# Whitespace_Daughtercard_pwr.net
KiCad netlist of a schematic drawn in Altium Designer
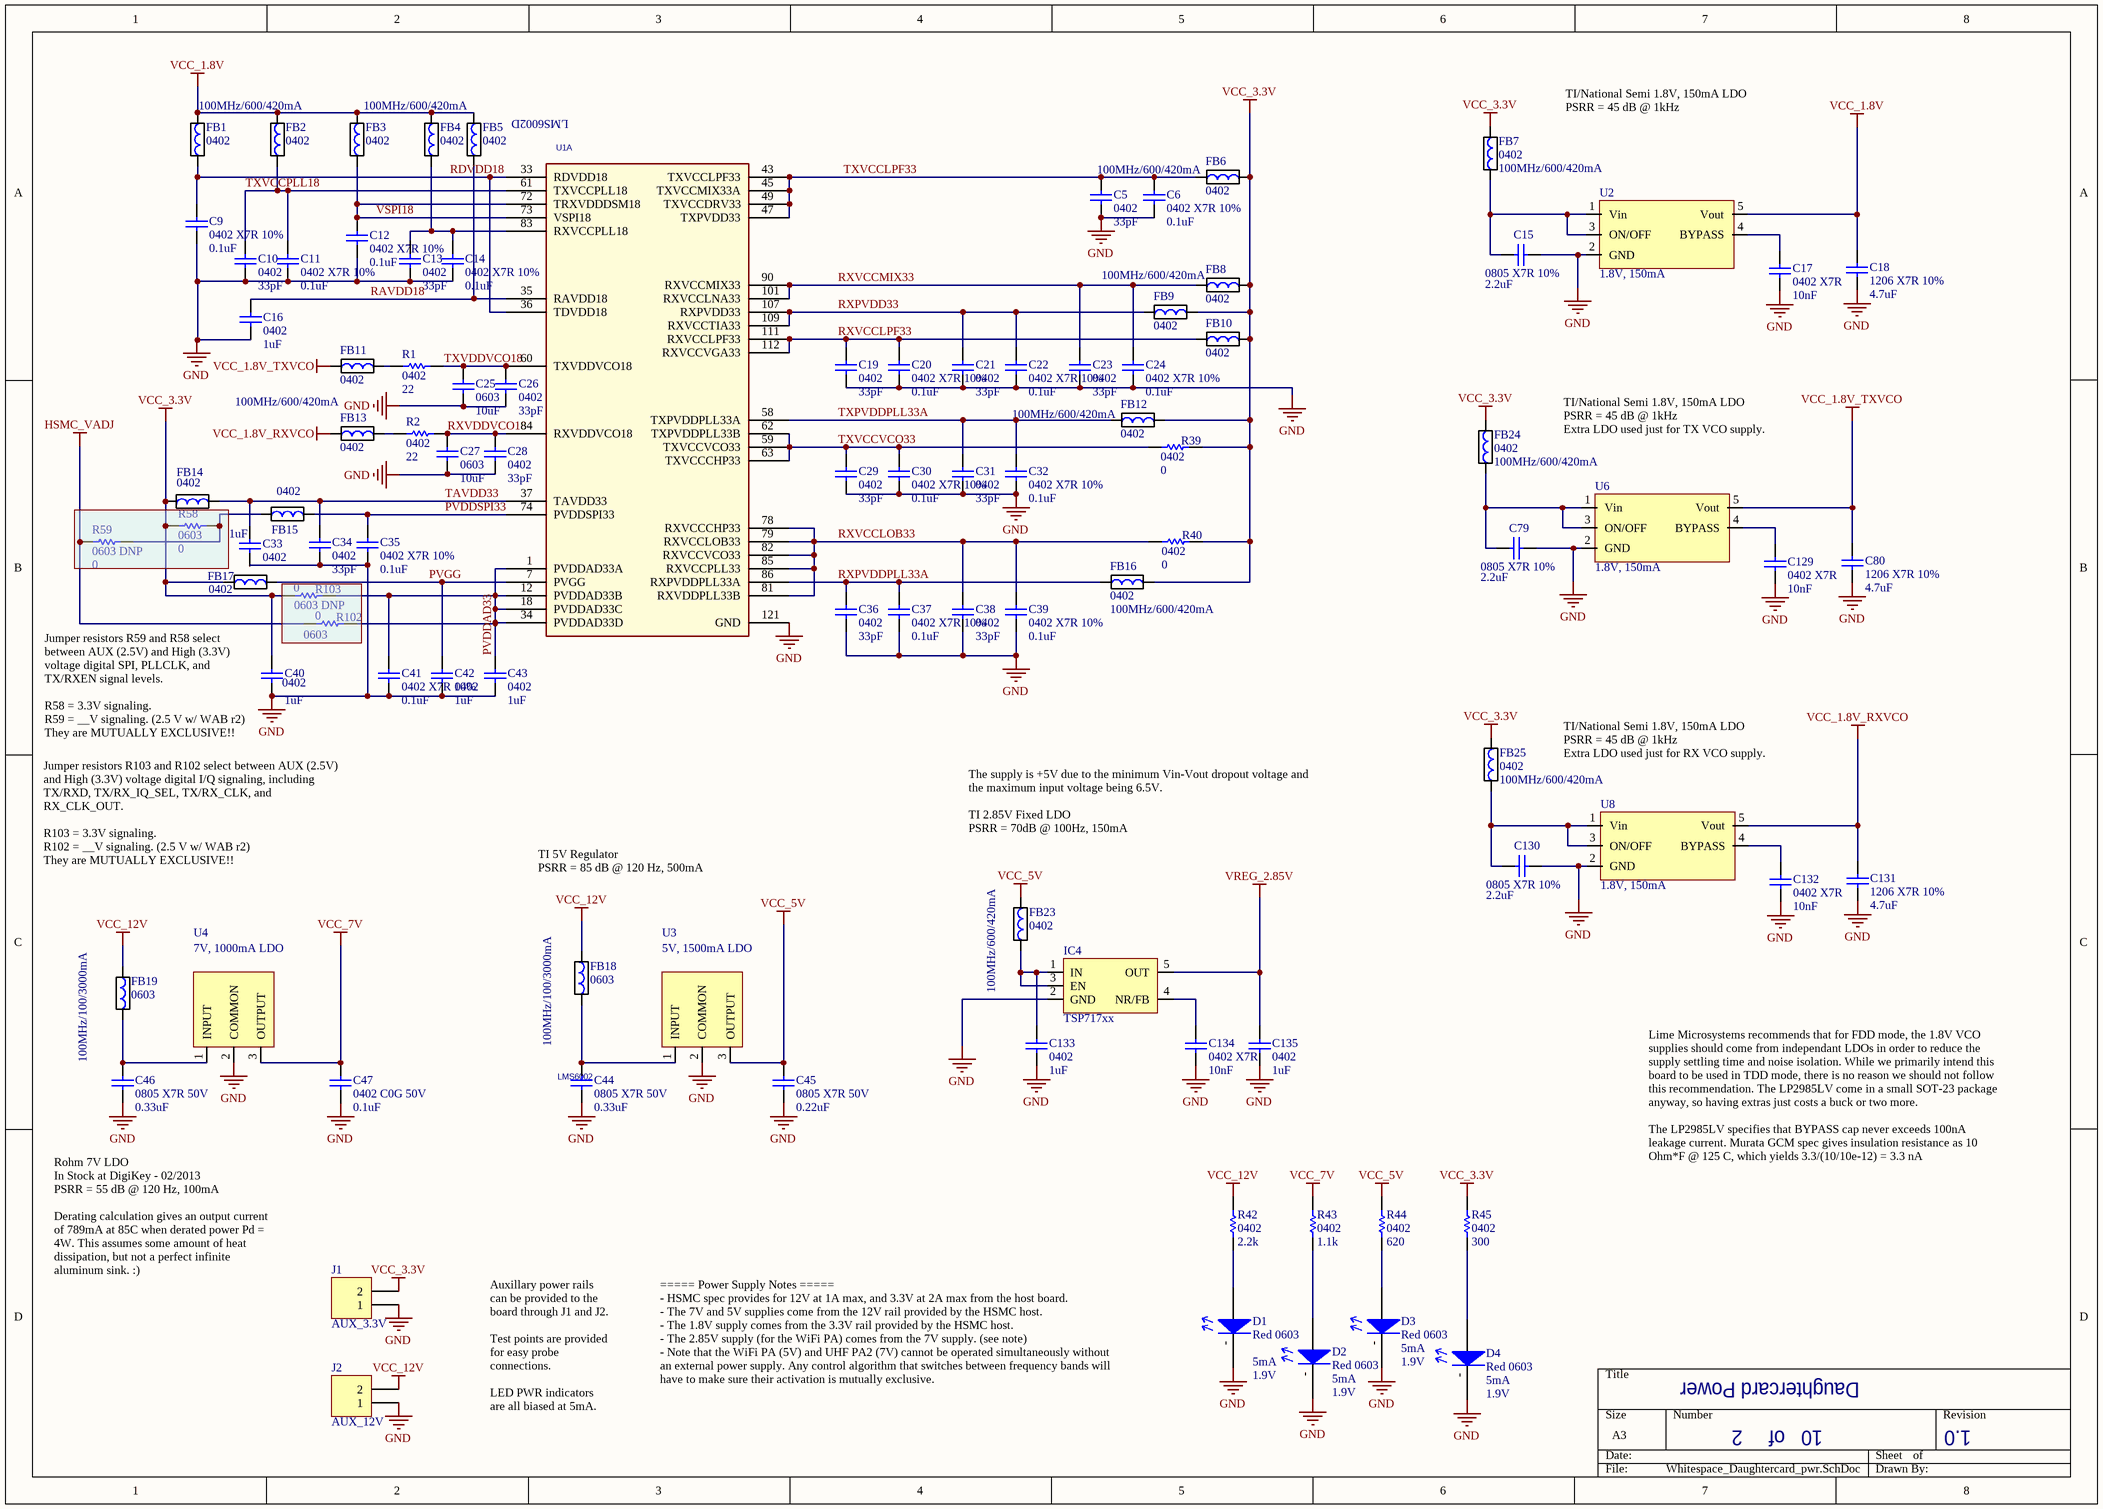
[diagram p0: Whitespace_Daughtercard_pwr.SchDoc]

(export (version "E")
  (design (tool "Eeschema 10.0.6"))
  (components
    (comp (ref "C5")
      (value "0402")
      (footprint "0402_SMT_v3")
      (description "Capacitor (Semiconductor SIM Model)")
      (fields (field (name "ALTIUM_VALUE") "33pF") (field (name "PUBLISHER") "Altium Limited"))
      (libsource (lib "Miscellaneous Devices") (part "Cap Semi"))
    )
    (comp (ref "C6")
      (value "0402 X7R 10%")
      (footprint "0402_SMT_v3")
      (description "Capacitor (Semiconductor SIM Model)")
      (fields (field (name "ALTIUM_VALUE") "0.1uF") (field (name "PUBLISHER") "Altium Limited"))
      (libsource (lib "Miscellaneous Devices") (part "Cap Semi"))
    )
    (comp (ref "C9")
      (value "0402 X7R 10%")
      (footprint "0402_SMT_v3")
      (description "Capacitor (Semiconductor SIM Model)")
      (fields (field (name "ALTIUM_VALUE") "0.1uF") (field (name "PUBLISHER") "Altium Limited"))
      (libsource (lib "Miscellaneous Devices") (part "Cap Semi"))
    )
    (comp (ref "C10")
      (value "0402")
      (footprint "0402_SMT_v3")
      (description "Capacitor (Semiconductor SIM Model)")
      (fields (field (name "ALTIUM_VALUE") "33pF") (field (name "PUBLISHER") "Altium Limited"))
      (libsource (lib "Miscellaneous Devices") (part "Cap Semi"))
    )
    (comp (ref "C11")
      (value "0402 X7R 10%")
      (footprint "0402_SMT_v3")
      (description "Capacitor (Semiconductor SIM Model)")
      (fields (field (name "ALTIUM_VALUE") "0.1uF") (field (name "PUBLISHER") "Altium Limited"))
      (libsource (lib "Miscellaneous Devices") (part "Cap Semi"))
    )
    (comp (ref "C12")
      (value "0402 X7R 10%")
      (footprint "0402_SMT_v3")
      (description "Capacitor (Semiconductor SIM Model)")
      (fields (field (name "ALTIUM_VALUE") "0.1uF") (field (name "PUBLISHER") "Altium Limited"))
      (libsource (lib "Miscellaneous Devices") (part "Cap Semi"))
    )
    (comp (ref "C13")
      (value "0402")
      (footprint "0402_SMT_v3")
      (description "Capacitor (Semiconductor SIM Model)")
      (fields (field (name "ALTIUM_VALUE") "33pF") (field (name "PUBLISHER") "Altium Limited"))
      (libsource (lib "Miscellaneous Devices") (part "Cap Semi"))
    )
    (comp (ref "C14")
      (value "0402 X7R 10%")
      (footprint "0402_SMT_v3")
      (description "Capacitor (Semiconductor SIM Model)")
      (fields (field (name "ALTIUM_VALUE") "0.1uF") (field (name "PUBLISHER") "Altium Limited"))
      (libsource (lib "Miscellaneous Devices") (part "Cap Semi"))
    )
    (comp (ref "C15")
      (value "0805 X7R 10%")
      (footprint "0805_SMT_v3")
      (description "Capacitor (Semiconductor SIM Model)")
      (fields (field (name "ALTIUM_VALUE") "2.2uF") (field (name "PUBLISHER") "Altium Limited"))
      (libsource (lib "Miscellaneous Devices") (part "Cap Semi"))
    )
    (comp (ref "C16")
      (value "0402")
      (footprint "0402_SMT_v3")
      (description "Capacitor (Semiconductor SIM Model)")
      (fields (field (name "ALTIUM_VALUE") "1uF") (field (name "PUBLISHER") "Altium Limited"))
      (libsource (lib "Miscellaneous Devices") (part "Cap Semi"))
    )
    (comp (ref "C17")
      (value "0402 X7R")
      (footprint "0402_SMT_v3")
      (description "Capacitor (Semiconductor SIM Model)")
      (fields (field (name "ALTIUM_VALUE") "10nF") (field (name "PUBLISHER") "Altium Limited"))
      (libsource (lib "Miscellaneous Devices") (part "Cap Semi"))
    )
    (comp (ref "C18")
      (value "1206 X7R 10%")
      (footprint "1206_SMT_v3")
      (description "Capacitor (Semiconductor SIM Model)")
      (fields (field (name "ALTIUM_VALUE") "4.7uF") (field (name "PUBLISHER") "Altium Limited"))
      (libsource (lib "Miscellaneous Devices") (part "Cap Semi"))
    )
    (comp (ref "C19")
      (value "0402")
      (footprint "0402_SMT_v3")
      (description "Capacitor (Semiconductor SIM Model)")
      (fields (field (name "ALTIUM_VALUE") "33pF") (field (name "PUBLISHER") "Altium Limited"))
      (libsource (lib "Miscellaneous Devices") (part "Cap Semi"))
    )
    (comp (ref "C20")
      (value "0402 X7R 10%")
      (footprint "0402_SMT_v3")
      (description "Capacitor (Semiconductor SIM Model)")
      (fields (field (name "ALTIUM_VALUE") "0.1uF") (field (name "PUBLISHER") "Altium Limited"))
      (libsource (lib "Miscellaneous Devices") (part "Cap Semi"))
    )
    (comp (ref "C21")
      (value "0402")
      (footprint "0402_SMT_v3")
      (description "Capacitor (Semiconductor SIM Model)")
      (fields (field (name "ALTIUM_VALUE") "33pF") (field (name "PUBLISHER") "Altium Limited"))
      (libsource (lib "Miscellaneous Devices") (part "Cap Semi"))
    )
    (comp (ref "C22")
      (value "0402 X7R 10%")
      (footprint "0402_SMT_v3")
      (description "Capacitor (Semiconductor SIM Model)")
      (fields (field (name "ALTIUM_VALUE") "0.1uF") (field (name "PUBLISHER") "Altium Limited"))
      (libsource (lib "Miscellaneous Devices") (part "Cap Semi"))
    )
    (comp (ref "C23")
      (value "0402")
      (footprint "0402_SMT_v3")
      (description "Capacitor (Semiconductor SIM Model)")
      (fields (field (name "ALTIUM_VALUE") "33pF") (field (name "PUBLISHER") "Altium Limited"))
      (libsource (lib "Miscellaneous Devices") (part "Cap Semi"))
    )
    (comp (ref "C24")
      (value "0402 X7R 10%")
      (footprint "0402_SMT_v3")
      (description "Capacitor (Semiconductor SIM Model)")
      (fields (field (name "ALTIUM_VALUE") "0.1uF") (field (name "PUBLISHER") "Altium Limited"))
      (libsource (lib "Miscellaneous Devices") (part "Cap Semi"))
    )
    (comp (ref "C25")
      (value "0603")
      (footprint "0603_SMT_v3")
      (description "Capacitor (Semiconductor SIM Model)")
      (fields (field (name "ALTIUM_VALUE") "10uF") (field (name "PUBLISHER") "Altium Limited"))
      (libsource (lib "Miscellaneous Devices") (part "Cap Semi"))
    )
    (comp (ref "C26")
      (value "0402")
      (footprint "0402_SMT_v3")
      (description "Capacitor (Semiconductor SIM Model)")
      (fields (field (name "ALTIUM_VALUE") "33pF") (field (name "PUBLISHER") "Altium Limited"))
      (libsource (lib "Miscellaneous Devices") (part "Cap Semi"))
    )
    (comp (ref "C27")
      (value "0603")
      (footprint "0603_SMT_v3")
      (description "Capacitor (Semiconductor SIM Model)")
      (fields (field (name "ALTIUM_VALUE") "10uF") (field (name "PUBLISHER") "Altium Limited"))
      (libsource (lib "Miscellaneous Devices") (part "Cap Semi"))
    )
    (comp (ref "C28")
      (value "0402")
      (footprint "0402_SMT_v3")
      (description "Capacitor (Semiconductor SIM Model)")
      (fields (field (name "ALTIUM_VALUE") "33pF") (field (name "PUBLISHER") "Altium Limited"))
      (libsource (lib "Miscellaneous Devices") (part "Cap Semi"))
    )
    (comp (ref "C29")
      (value "0402")
      (footprint "0402_SMT_v3")
      (description "Capacitor (Semiconductor SIM Model)")
      (fields (field (name "ALTIUM_VALUE") "33pF") (field (name "PUBLISHER") "Altium Limited"))
      (libsource (lib "Miscellaneous Devices") (part "Cap Semi"))
    )
    (comp (ref "C30")
      (value "0402 X7R 10%")
      (footprint "0402_SMT_v3")
      (description "Capacitor (Semiconductor SIM Model)")
      (fields (field (name "ALTIUM_VALUE") "0.1uF") (field (name "PUBLISHER") "Altium Limited"))
      (libsource (lib "Miscellaneous Devices") (part "Cap Semi"))
    )
    (comp (ref "C31")
      (value "0402")
      (footprint "0402_SMT_v3")
      (description "Capacitor (Semiconductor SIM Model)")
      (fields (field (name "ALTIUM_VALUE") "33pF") (field (name "PUBLISHER") "Altium Limited"))
      (libsource (lib "Miscellaneous Devices") (part "Cap Semi"))
    )
    (comp (ref "C32")
      (value "0402 X7R 10%")
      (footprint "0402_SMT_v3")
      (description "Capacitor (Semiconductor SIM Model)")
      (fields (field (name "ALTIUM_VALUE") "0.1uF") (field (name "PUBLISHER") "Altium Limited"))
      (libsource (lib "Miscellaneous Devices") (part "Cap Semi"))
    )
    (comp (ref "C33")
      (value "0402")
      (footprint "0402_SMT_v3")
      (description "Capacitor (Semiconductor SIM Model)")
      (fields (field (name "ALTIUM_VALUE") "1uF") (field (name "PUBLISHER") "Altium Limited"))
      (libsource (lib "Miscellaneous Devices") (part "Cap Semi"))
    )
    (comp (ref "C34")
      (value "0402")
      (footprint "0402_SMT_v3")
      (description "Capacitor (Semiconductor SIM Model)")
      (fields (field (name "ALTIUM_VALUE") "33pF") (field (name "PUBLISHER") "Altium Limited"))
      (libsource (lib "Miscellaneous Devices") (part "Cap Semi"))
    )
    (comp (ref "C35")
      (value "0402 X7R 10%")
      (footprint "0402_SMT_v3")
      (description "Capacitor (Semiconductor SIM Model)")
      (fields (field (name "ALTIUM_VALUE") "0.1uF") (field (name "PUBLISHER") "Altium Limited"))
      (libsource (lib "Miscellaneous Devices") (part "Cap Semi"))
    )
    (comp (ref "C36")
      (value "0402")
      (footprint "0402_SMT_v3")
      (description "Capacitor (Semiconductor SIM Model)")
      (fields (field (name "ALTIUM_VALUE") "33pF") (field (name "PUBLISHER") "Altium Limited"))
      (libsource (lib "Miscellaneous Devices") (part "Cap Semi"))
    )
    (comp (ref "C37")
      (value "0402 X7R 10%")
      (footprint "0402_SMT_v3")
      (description "Capacitor (Semiconductor SIM Model)")
      (fields (field (name "ALTIUM_VALUE") "0.1uF") (field (name "PUBLISHER") "Altium Limited"))
      (libsource (lib "Miscellaneous Devices") (part "Cap Semi"))
    )
    (comp (ref "C38")
      (value "0402")
      (footprint "0402_SMT_v3")
      (description "Capacitor (Semiconductor SIM Model)")
      (fields (field (name "ALTIUM_VALUE") "33pF") (field (name "PUBLISHER") "Altium Limited"))
      (libsource (lib "Miscellaneous Devices") (part "Cap Semi"))
    )
    (comp (ref "C39")
      (value "0402 X7R 10%")
      (footprint "0402_SMT_v3")
      (description "Capacitor (Semiconductor SIM Model)")
      (fields (field (name "ALTIUM_VALUE") "0.1uF") (field (name "PUBLISHER") "Altium Limited"))
      (libsource (lib "Miscellaneous Devices") (part "Cap Semi"))
    )
    (comp (ref "C40")
      (value "0402")
      (footprint "0402_SMT_v3")
      (description "Capacitor (Semiconductor SIM Model)")
      (fields (field (name "ALTIUM_VALUE") "1uF") (field (name "PUBLISHER") "Altium Limited"))
      (libsource (lib "Miscellaneous Devices") (part "Cap Semi"))
    )
    (comp (ref "C41")
      (value "0402 X7R 10%")
      (footprint "0402_SMT_v3")
      (description "Capacitor (Semiconductor SIM Model)")
      (fields (field (name "ALTIUM_VALUE") "0.1uF") (field (name "PUBLISHER") "Altium Limited"))
      (libsource (lib "Miscellaneous Devices") (part "Cap Semi"))
    )
    (comp (ref "C42")
      (value "0402")
      (footprint "0402_SMT_v3")
      (description "Capacitor (Semiconductor SIM Model)")
      (fields (field (name "ALTIUM_VALUE") "1uF") (field (name "PUBLISHER") "Altium Limited"))
      (libsource (lib "Miscellaneous Devices") (part "Cap Semi"))
    )
    (comp (ref "C43")
      (value "0402")
      (footprint "0402_SMT_v3")
      (description "Capacitor (Semiconductor SIM Model)")
      (fields (field (name "ALTIUM_VALUE") "1uF") (field (name "PUBLISHER") "Altium Limited"))
      (libsource (lib "Miscellaneous Devices") (part "Cap Semi"))
    )
    (comp (ref "C44")
      (value "0805 X7R 50V")
      (footprint "0805_SMT_v3")
      (description "Capacitor (Semiconductor SIM Model)")
      (fields (field (name "ALTIUM_VALUE") "0.33uF") (field (name "PUBLISHER") "Altium Limited"))
      (libsource (lib "Miscellaneous Devices") (part "Cap Semi"))
    )
    (comp (ref "C45")
      (value "0805 X7R 50V")
      (footprint "0805_SMT_v3")
      (description "Capacitor (Semiconductor SIM Model)")
      (fields (field (name "ALTIUM_VALUE") "0.22uF") (field (name "PUBLISHER") "Altium Limited"))
      (libsource (lib "Miscellaneous Devices") (part "Cap Semi"))
    )
    (comp (ref "C46")
      (value "0805 X7R 50V")
      (footprint "0805_SMT_v3")
      (description "Capacitor (Semiconductor SIM Model)")
      (fields (field (name "ALTIUM_VALUE") "0.33uF") (field (name "PUBLISHER") "Altium Limited"))
      (libsource (lib "Miscellaneous Devices") (part "Cap Semi"))
    )
    (comp (ref "C47")
      (value "0402 C0G 50V")
      (footprint "0402_SMT_v3")
      (description "Capacitor (Semiconductor SIM Model)")
      (fields (field (name "ALTIUM_VALUE") "0.1uF") (field (name "PUBLISHER") "Altium Limited"))
      (libsource (lib "Miscellaneous Devices") (part "Cap Semi"))
    )
    (comp (ref "C79")
      (value "0805 X7R 10%")
      (footprint "0805_SMT_v3")
      (description "Capacitor (Semiconductor SIM Model)")
      (fields (field (name "ALTIUM_VALUE") "2.2uF") (field (name "PUBLISHER") "Altium Limited"))
      (libsource (lib "Miscellaneous Devices") (part "Cap Semi"))
    )
    (comp (ref "C80")
      (value "1206 X7R 10%")
      (footprint "1206_SMT_v3")
      (description "Capacitor (Semiconductor SIM Model)")
      (fields (field (name "ALTIUM_VALUE") "4.7uF") (field (name "PUBLISHER") "Altium Limited"))
      (libsource (lib "Miscellaneous Devices") (part "Cap Semi"))
    )
    (comp (ref "C129")
      (value "0402 X7R")
      (footprint "0402_SMT_v3")
      (description "Capacitor (Semiconductor SIM Model)")
      (fields (field (name "ALTIUM_VALUE") "10nF") (field (name "PUBLISHER") "Altium Limited"))
      (libsource (lib "Miscellaneous Devices") (part "Cap Semi"))
    )
    (comp (ref "C130")
      (value "0805 X7R 10%")
      (footprint "0805_SMT_v3")
      (description "Capacitor (Semiconductor SIM Model)")
      (fields (field (name "ALTIUM_VALUE") "2.2uF") (field (name "PUBLISHER") "Altium Limited"))
      (libsource (lib "Miscellaneous Devices") (part "Cap Semi"))
    )
    (comp (ref "C131")
      (value "1206 X7R 10%")
      (footprint "1206_SMT_v3")
      (description "Capacitor (Semiconductor SIM Model)")
      (fields (field (name "ALTIUM_VALUE") "4.7uF") (field (name "PUBLISHER") "Altium Limited"))
      (libsource (lib "Miscellaneous Devices") (part "Cap Semi"))
    )
    (comp (ref "C132")
      (value "0402 X7R")
      (footprint "0402_SMT_v3")
      (description "Capacitor (Semiconductor SIM Model)")
      (fields (field (name "ALTIUM_VALUE") "10nF") (field (name "PUBLISHER") "Altium Limited"))
      (libsource (lib "Miscellaneous Devices") (part "Cap Semi"))
    )
    (comp (ref "C133")
      (value "0402")
      (footprint "0402_SMT_v3")
      (description "Capacitor (Semiconductor SIM Model)")
      (fields (field (name "ALTIUM_VALUE") "1uF") (field (name "PUBLISHER") "Altium Limited"))
      (libsource (lib "Miscellaneous Devices") (part "Cap Semi"))
    )
    (comp (ref "C134")
      (value "0402 X7R")
      (footprint "0402_SMT_v3")
      (description "Capacitor (Semiconductor SIM Model)")
      (fields (field (name "ALTIUM_VALUE") "10nF") (field (name "PUBLISHER") "Altium Limited"))
      (libsource (lib "Miscellaneous Devices") (part "Cap Semi"))
    )
    (comp (ref "C135")
      (value "0402")
      (footprint "0402_SMT_v3")
      (description "Capacitor (Semiconductor SIM Model)")
      (fields (field (name "ALTIUM_VALUE") "1uF") (field (name "PUBLISHER") "Altium Limited"))
      (libsource (lib "Miscellaneous Devices") (part "Cap Semi"))
    )
    (comp (ref "D1")
      (value "Red 0603")
      (footprint "0603_POLAR")
      (fields (field (name "CURRENT") "5mA") (field (name "FORWARD VOLTAGE DROP") "1.9V"))
      (libsource (lib "RNG_Parts") (part "LED"))
    )
    (comp (ref "D2")
      (value "Red 0603")
      (footprint "0603_POLAR")
      (fields (field (name "CURRENT") "5mA") (field (name "FORWARD VOLTAGE DROP") "1.9V"))
      (libsource (lib "RNG_Parts") (part "LED"))
    )
    (comp (ref "D3")
      (value "Red 0603")
      (footprint "0603_POLAR")
      (fields (field (name "CURRENT") "5mA") (field (name "FORWARD VOLTAGE DROP") "1.9V"))
      (libsource (lib "RNG_Parts") (part "LED"))
    )
    (comp (ref "D4")
      (value "Red 0603")
      (footprint "0603_POLAR")
      (fields (field (name "CURRENT") "5mA") (field (name "FORWARD VOLTAGE DROP") "1.9V"))
      (libsource (lib "RNG_Parts") (part "LED"))
    )
    (comp (ref "FB1")
      (value "0402")
      (footprint "0402_SMT_v3")
      (description "Ferrite Bead, Various Values")
      (fields (field (name "ALTIUM_VALUE") "100MHz/600/420mA"))
      (libsource (lib "RNG_Parts") (part "FERRITE_BEAD"))
    )
    (comp (ref "FB2")
      (value "0402")
      (footprint "0402_SMT_v3")
      (description "Ferrite Bead, Various Values")
      (libsource (lib "RNG_Parts") (part "FERRITE_BEAD"))
    )
    (comp (ref "FB3")
      (value "0402")
      (footprint "0402_SMT_v3")
      (description "Ferrite Bead, Various Values")
      (libsource (lib "RNG_Parts") (part "FERRITE_BEAD"))
    )
    (comp (ref "FB4")
      (value "0402")
      (footprint "0402_SMT_v3")
      (description "Ferrite Bead, Various Values")
      (libsource (lib "RNG_Parts") (part "FERRITE_BEAD"))
    )
    (comp (ref "FB5")
      (value "0402")
      (footprint "0402_SMT_v3")
      (description "Ferrite Bead, Various Values")
      (fields (field (name "ALTIUM_VALUE") "100MHz/600/420mA"))
      (libsource (lib "RNG_Parts") (part "FERRITE_BEAD"))
    )
    (comp (ref "FB6")
      (value "0402")
      (footprint "0402_SMT_v3")
      (description "Ferrite Bead, Various Values")
      (fields (field (name "ALTIUM_VALUE") "100MHz/600/420mA"))
      (libsource (lib "RNG_Parts") (part "FERRITE_BEAD"))
    )
    (comp (ref "FB7")
      (value "0402")
      (footprint "0402_SMT_v3")
      (description "Ferrite Bead, Various Values")
      (fields (field (name "ALTIUM_VALUE") "100MHz/600/420mA"))
      (libsource (lib "RNG_Parts") (part "FERRITE_BEAD"))
    )
    (comp (ref "FB8")
      (value "0402")
      (footprint "0402_SMT_v3")
      (description "Ferrite Bead, Various Values")
      (libsource (lib "RNG_Parts") (part "FERRITE_BEAD"))
    )
    (comp (ref "FB9")
      (value "0402")
      (footprint "0402_SMT_v3")
      (description "Ferrite Bead, Various Values")
      (fields (field (name "ALTIUM_VALUE") "100MHz/600/420mA"))
      (libsource (lib "RNG_Parts") (part "FERRITE_BEAD"))
    )
    (comp (ref "FB10")
      (value "0402")
      (footprint "0402_SMT_v3")
      (description "Ferrite Bead, Various Values")
      (libsource (lib "RNG_Parts") (part "FERRITE_BEAD"))
    )
    (comp (ref "FB11")
      (value "0402")
      (footprint "0402_SMT_v3")
      (description "Ferrite Bead, Various Values")
      (libsource (lib "RNG_Parts") (part "FERRITE_BEAD"))
    )
    (comp (ref "FB12")
      (value "0402")
      (footprint "0402_SMT_v3")
      (description "Ferrite Bead, Various Values")
      (fields (field (name "ALTIUM_VALUE") "100MHz/600/420mA"))
      (libsource (lib "RNG_Parts") (part "FERRITE_BEAD"))
    )
    (comp (ref "FB13")
      (value "0402")
      (footprint "0402_SMT_v3")
      (description "Ferrite Bead, Various Values")
      (fields (field (name "ALTIUM_VALUE") "100MHz/600/420mA"))
      (libsource (lib "RNG_Parts") (part "FERRITE_BEAD"))
    )
    (comp (ref "FB14")
      (value "0402")
      (footprint "0402_SMT_v3")
      (description "Ferrite Bead, Various Values")
      (libsource (lib "RNG_Parts") (part "FERRITE_BEAD"))
    )
    (comp (ref "FB15")
      (value "0402")
      (footprint "0402_SMT_v3")
      (description "Ferrite Bead, Various Values")
      (libsource (lib "RNG_Parts") (part "FERRITE_BEAD"))
    )
    (comp (ref "FB16")
      (value "0402")
      (footprint "0402_SMT_v3")
      (description "Ferrite Bead, Various Values")
      (fields (field (name "ALTIUM_VALUE") "100MHz/600/420mA"))
      (libsource (lib "RNG_Parts") (part "FERRITE_BEAD"))
    )
    (comp (ref "FB17")
      (value "0402")
      (footprint "0402_SMT_v3")
      (description "Ferrite Bead, Various Values")
      (libsource (lib "RNG_Parts") (part "FERRITE_BEAD"))
    )
    (comp (ref "FB18")
      (value "0603")
      (footprint "0603_SMT_v3")
      (description "Ferrite Bead, Various Values")
      (fields (field (name "ALTIUM_VALUE") "100MHz/100/3000mA"))
      (libsource (lib "RNG_Parts") (part "FERRITE_BEAD"))
    )
    (comp (ref "FB19")
      (value "0603")
      (footprint "0603_SMT_v3")
      (description "Ferrite Bead, Various Values")
      (fields (field (name "ALTIUM_VALUE") "100MHz/100/3000mA"))
      (libsource (lib "RNG_Parts") (part "FERRITE_BEAD"))
    )
    (comp (ref "FB23")
      (value "0402")
      (footprint "0402_SMT_v3")
      (description "Ferrite Bead, Various Values")
      (fields (field (name "ALTIUM_VALUE") "100MHz/600/420mA"))
      (libsource (lib "RNG_Parts") (part "FERRITE_BEAD"))
    )
    (comp (ref "FB24")
      (value "0402")
      (footprint "0402_SMT_v3")
      (description "Ferrite Bead, Various Values")
      (fields (field (name "ALTIUM_VALUE") "100MHz/600/420mA"))
      (libsource (lib "RNG_Parts") (part "FERRITE_BEAD"))
    )
    (comp (ref "FB25")
      (value "0402")
      (footprint "0402_SMT_v3")
      (description "Ferrite Bead, Various Values")
      (fields (field (name "ALTIUM_VALUE") "100MHz/600/420mA"))
      (libsource (lib "RNG_Parts") (part "FERRITE_BEAD"))
    )
    (comp (ref "IC4")
      (value "TSP717xx")
      (footprint "SC70-5")
      (description "TI LDO Regulator SC70-5 0.9-6.2V")
      (libsource (lib "RNG_Parts") (part "TSP717xx"))
    )
    (comp (ref "J1")
      (value "AUX_3.3V")
      (footprint "HDR1X2")
      (description "Header, 2-Pin")
      (fields (field (name "PUBLISHER") "Altium Limited"))
      (libsource (lib "Miscellaneous Connectors") (part "Header 2"))
    )
    (comp (ref "J2")
      (value "AUX_12V")
      (footprint "HDR1X2")
      (description "Header, 2-Pin")
      (fields (field (name "PUBLISHER") "Altium Limited"))
      (libsource (lib "Miscellaneous Connectors") (part "Header 2"))
    )
    (comp (ref "R1")
      (value "0402")
      (footprint "0402_SMT_v3")
      (description "Semiconductor Resistor")
      (fields (field (name "ALTIUM_VALUE") "22") (field (name "PUBLISHER") "Altium Limited"))
      (libsource (lib "Miscellaneous Devices") (part "Res Semi"))
    )
    (comp (ref "R2")
      (value "0402")
      (footprint "0402_SMT_v3")
      (description "Semiconductor Resistor")
      (fields (field (name "ALTIUM_VALUE") "22") (field (name "PUBLISHER") "Altium Limited"))
      (libsource (lib "Miscellaneous Devices") (part "Res Semi"))
    )
    (comp (ref "R39")
      (value "0402")
      (footprint "0402_SMT_v3")
      (description "Semiconductor Resistor")
      (fields (field (name "ALTIUM_VALUE") "0") (field (name "PUBLISHER") "Altium Limited"))
      (libsource (lib "Miscellaneous Devices") (part "Res Semi"))
    )
    (comp (ref "R40")
      (value "0402")
      (footprint "0402_SMT_v3")
      (description "Semiconductor Resistor")
      (fields (field (name "ALTIUM_VALUE") "0") (field (name "PUBLISHER") "Altium Limited"))
      (libsource (lib "Miscellaneous Devices") (part "Res Semi"))
    )
    (comp (ref "R42")
      (value "0402")
      (footprint "0402_SMT_v3")
      (description "Semiconductor Resistor")
      (fields (field (name "ALTIUM_VALUE") "2.2k") (field (name "PUBLISHER") "Altium Limited"))
      (libsource (lib "Miscellaneous Devices") (part "Res Semi"))
    )
    (comp (ref "R43")
      (value "0402")
      (footprint "0402_SMT_v3")
      (description "Semiconductor Resistor")
      (fields (field (name "ALTIUM_VALUE") "1.1k") (field (name "PUBLISHER") "Altium Limited"))
      (libsource (lib "Miscellaneous Devices") (part "Res Semi"))
    )
    (comp (ref "R44")
      (value "0402")
      (footprint "0402_SMT_v3")
      (description "Semiconductor Resistor")
      (fields (field (name "ALTIUM_VALUE") "620") (field (name "PUBLISHER") "Altium Limited"))
      (libsource (lib "Miscellaneous Devices") (part "Res Semi"))
    )
    (comp (ref "R45")
      (value "0402")
      (footprint "0402_SMT_v3")
      (description "Semiconductor Resistor")
      (fields (field (name "ALTIUM_VALUE") "300") (field (name "PUBLISHER") "Altium Limited"))
      (libsource (lib "Miscellaneous Devices") (part "Res Semi"))
    )
    (comp (ref "R58")
      (value "0603")
      (footprint "0603_SMT_v3")
      (description "Semiconductor Resistor")
      (fields (field (name "ALTIUM_VALUE") "0") (field (name "PUBLISHER") "Altium Limited"))
      (libsource (lib "Miscellaneous Devices") (part "Res Semi"))
    )
    (comp (ref "R59")
      (value "0603 DNP")
      (footprint "0603_SMT_v3")
      (description "Semiconductor Resistor")
      (fields (field (name "ALTIUM_VALUE") "0") (field (name "PUBLISHER") "Altium Limited"))
      (libsource (lib "Miscellaneous Devices") (part "Res Semi"))
    )
    (comp (ref "R102")
      (value "0603")
      (footprint "0603_SMT_v3")
      (description "Semiconductor Resistor")
      (fields (field (name "ALTIUM_VALUE") "0") (field (name "PUBLISHER") "Altium Limited"))
      (libsource (lib "Miscellaneous Devices") (part "Res Semi"))
    )
    (comp (ref "R103")
      (value "0603 DNP")
      (footprint "0603_SMT_v3")
      (description "Semiconductor Resistor")
      (fields (field (name "ALTIUM_VALUE") "0") (field (name "PUBLISHER") "Altium Limited"))
      (libsource (lib "Miscellaneous Devices") (part "Res Semi"))
    )
    (comp (ref "U1")
      (value "LMS6002")
      (footprint "LMS6002D_VIAOFFPAD_v2_Window")
      (description "Lime Microsystems Wideband Transceiver Module")
      (libsource (lib "RNG_Parts") (part "LMS6002"))
    )
    (comp (ref "U2")
      (value "1.8V, 150mA")
      (footprint "SOT-23_5Lead")
      (description "TO LDO 1.8V 150mA Regulator w/ ON/OFF")
      (libsource (lib "RNG_Parts") (part "LP2985IM5-1.8"))
    )
    (comp (ref "U3")
      (value "5V, 1500mA LDO")
      (footprint "TO-263")
      (description "TI 5V, 1500mA LDO")
      (libsource (lib "RNG_Parts") (part "TL780-05CKTTRG3"))
    )
    (comp (ref "U4")
      (value "7V, 1000mA LDO")
      (footprint "TO252-3")
      (description "ROHM 7V, 1000mA LDO")
      (libsource (lib "RNG_Parts") (part "BA7807FP"))
    )
    (comp (ref "U6")
      (value "1.8V, 150mA")
      (footprint "SOT-23_5Lead")
      (description "TO LDO 1.8V 150mA Regulator w/ ON/OFF")
      (libsource (lib "RNG_Parts") (part "LP2985IM5-1.8"))
    )
    (comp (ref "U8")
      (value "1.8V, 150mA")
      (footprint "SOT-23_5Lead")
      (description "TO LDO 1.8V 150mA Regulator w/ ON/OFF")
      (libsource (lib "RNG_Parts") (part "LP2985IM5-1.8"))
    )
  )
  (nets
    (net (code "1") (name "/PVDDAD33") (class "Default")
      (node (ref "C41") (pin "2") (pinfunction "2_2") (pintype "passive"))
      (node (ref "C43") (pin "2") (pinfunction "2_2") (pintype "passive"))
      (node (ref "R102") (pin "1") (pinfunction "1_1") (pintype "passive"))
      (node (ref "R103") (pin "1") (pinfunction "1_1") (pintype "passive"))
      (node (ref "U1") (pin "1") (pinfunction "PVDDAD33A_1") (pintype "passive"))
      (node (ref "U1") (pin "12") (pinfunction "PVDDAD33B_12") (pintype "passive"))
      (node (ref "U1") (pin "18") (pinfunction "PVDDAD33C_18") (pintype "passive"))
      (node (ref "U1") (pin "34") (pinfunction "PVDDAD33D_34") (pintype "passive"))
    )
    (net (code "2") (name "/PVDDSPI33") (class "Default")
      (node (ref "C35") (pin "1") (pinfunction "1_1") (pintype "passive"))
      (node (ref "FB15") (pin "2") (pinfunction "2_2") (pintype "passive"))
      (node (ref "U1") (pin "74") (pinfunction "PVDDSPI33_74") (pintype "passive"))
    )
    (net (code "3") (name "/PVGG") (class "Default")
      (node (ref "C42") (pin "2") (pinfunction "2_2") (pintype "passive"))
      (node (ref "FB17") (pin "2") (pinfunction "2_2") (pintype "passive"))
      (node (ref "U1") (pin "7") (pinfunction "PVGG_7") (pintype "passive"))
    )
    (net (code "4") (name "/RAVDD18") (class "Default")
      (node (ref "C16") (pin "1") (pinfunction "1_1") (pintype "passive"))
      (node (ref "FB5") (pin "1") (pinfunction "1_1") (pintype "passive"))
      (node (ref "U1") (pin "35") (pinfunction "RAVDD18_35") (pintype "passive"))
    )
    (net (code "5") (name "/RDVDD18") (class "Default")
      (node (ref "C9") (pin "2") (pinfunction "2_2") (pintype "passive"))
      (node (ref "FB1") (pin "1") (pinfunction "1_1") (pintype "passive"))
      (node (ref "U1") (pin "33") (pinfunction "RDVDD18_33") (pintype "passive"))
      (node (ref "U1") (pin "36") (pinfunction "TDVDD18_36") (pintype "passive"))
    )
    (net (code "6") (name "/RXPVDD33") (class "Default")
      (node (ref "C21") (pin "1") (pinfunction "1_1") (pintype "passive"))
      (node (ref "C22") (pin "2") (pinfunction "2_2") (pintype "passive"))
      (node (ref "FB9") (pin "1") (pinfunction "1_1") (pintype "passive"))
      (node (ref "U1") (pin "107") (pinfunction "RXPVDD33_107") (pintype "passive"))
      (node (ref "U1") (pin "109") (pinfunction "RXVCCTIA33_109") (pintype "passive"))
    )
    (net (code "7") (name "/RXPVDDPLL33A") (class "Default")
      (node (ref "C36") (pin "1") (pinfunction "1_1") (pintype "passive"))
      (node (ref "C37") (pin "2") (pinfunction "2_2") (pintype "passive"))
      (node (ref "FB16") (pin "1") (pinfunction "1_1") (pintype "passive"))
      (node (ref "U1") (pin "86") (pinfunction "RXPVDDPLL33A_86") (pintype "passive"))
    )
    (net (code "8") (name "/RXVCCLOB33") (class "Default")
      (node (ref "C38") (pin "1") (pinfunction "1_1") (pintype "passive"))
      (node (ref "C39") (pin "2") (pinfunction "2_2") (pintype "passive"))
      (node (ref "R40") (pin "2") (pinfunction "2_2") (pintype "passive"))
      (node (ref "U1") (pin "78") (pinfunction "RXVCCCHP33_78") (pintype "passive"))
      (node (ref "U1") (pin "79") (pinfunction "RXVCCLOB33_79") (pintype "passive"))
      (node (ref "U1") (pin "81") (pinfunction "RXVDDPLL33B_81") (pintype "passive"))
      (node (ref "U1") (pin "82") (pinfunction "RXVCCVCO33_82") (pintype "passive"))
      (node (ref "U1") (pin "85") (pinfunction "RXVCCPLL33_85") (pintype "passive"))
    )
    (net (code "9") (name "/RXVCCLPF33") (class "Default")
      (node (ref "C19") (pin "1") (pinfunction "1_1") (pintype "passive"))
      (node (ref "C20") (pin "2") (pinfunction "2_2") (pintype "passive"))
      (node (ref "FB10") (pin "1") (pinfunction "1_1") (pintype "passive"))
      (node (ref "U1") (pin "111") (pinfunction "RXVCCLPF33_111") (pintype "passive"))
      (node (ref "U1") (pin "112") (pinfunction "RXVCCVGA33_112") (pintype "passive"))
    )
    (net (code "10") (name "/RXVCCMIX33") (class "Default")
      (node (ref "C23") (pin "1") (pinfunction "1_1") (pintype "passive"))
      (node (ref "C24") (pin "2") (pinfunction "2_2") (pintype "passive"))
      (node (ref "FB8") (pin "1") (pinfunction "1_1") (pintype "passive"))
      (node (ref "U1") (pin "101") (pinfunction "RXVCCLNA33_101") (pintype "passive"))
      (node (ref "U1") (pin "90") (pinfunction "RXVCCMIX33_90") (pintype "passive"))
    )
    (net (code "11") (name "/RXVDDVCO18") (class "Default")
      (node (ref "C27") (pin "2") (pinfunction "2_2") (pintype "passive"))
      (node (ref "C28") (pin "1") (pinfunction "1_1") (pintype "passive"))
      (node (ref "R2") (pin "1") (pinfunction "1_1") (pintype "passive"))
      (node (ref "U1") (pin "84") (pinfunction "RXVDDVCO18_84") (pintype "passive"))
    )
    (net (code "12") (name "/TAVDD33") (class "Default")
      (node (ref "C33") (pin "2") (pinfunction "2_2") (pintype "passive"))
      (node (ref "C34") (pin "2") (pinfunction "2_2") (pintype "passive"))
      (node (ref "FB14") (pin "2") (pinfunction "2_2") (pintype "passive"))
      (node (ref "U1") (pin "37") (pinfunction "TAVDD33_37") (pintype "passive"))
    )
    (net (code "13") (name "/TXPVDDPLL33A") (class "Default")
      (node (ref "C31") (pin "1") (pinfunction "1_1") (pintype "passive"))
      (node (ref "C32") (pin "2") (pinfunction "2_2") (pintype "passive"))
      (node (ref "FB12") (pin "1") (pinfunction "1_1") (pintype "passive"))
      (node (ref "U1") (pin "58") (pinfunction "TXPVDDPLL33A_58") (pintype "passive"))
    )
    (net (code "14") (name "/TXVCCLPF33") (class "Default")
      (node (ref "C5") (pin "1") (pinfunction "1_1") (pintype "passive"))
      (node (ref "C6") (pin "2") (pinfunction "2_2") (pintype "passive"))
      (node (ref "FB6") (pin "1") (pinfunction "1_1") (pintype "passive"))
      (node (ref "U1") (pin "43") (pinfunction "TXVCCLPF33_43") (pintype "passive"))
      (node (ref "U1") (pin "45") (pinfunction "TXVCCMIX33A_45") (pintype "passive"))
      (node (ref "U1") (pin "47") (pinfunction "TXPVDD33_47") (pintype "passive"))
      (node (ref "U1") (pin "49") (pinfunction "TXVCCDRV33_49") (pintype "passive"))
    )
    (net (code "15") (name "/TXVCCPLL18") (class "Default")
      (node (ref "C10") (pin "2") (pinfunction "2_2") (pintype "passive"))
      (node (ref "C11") (pin "2") (pinfunction "2_2") (pintype "passive"))
      (node (ref "FB2") (pin "1") (pinfunction "1_1") (pintype "passive"))
      (node (ref "U1") (pin "61") (pinfunction "TXVCCPLL18_61") (pintype "passive"))
    )
    (net (code "16") (name "/TXVCCVCO33") (class "Default")
      (node (ref "C29") (pin "1") (pinfunction "1_1") (pintype "passive"))
      (node (ref "C30") (pin "2") (pinfunction "2_2") (pintype "passive"))
      (node (ref "R39") (pin "2") (pinfunction "2_2") (pintype "passive"))
      (node (ref "U1") (pin "59") (pinfunction "TXVCCVCO33_59") (pintype "passive"))
      (node (ref "U1") (pin "62") (pinfunction "TXPVDDPLL33B_62") (pintype "passive"))
      (node (ref "U1") (pin "63") (pinfunction "TXVCCCHP33_63") (pintype "passive"))
    )
    (net (code "17") (name "/TXVDDVCO18") (class "Default")
      (node (ref "C25") (pin "2") (pinfunction "2_2") (pintype "passive"))
      (node (ref "C26") (pin "1") (pinfunction "1_1") (pintype "passive"))
      (node (ref "R1") (pin "1") (pinfunction "1_1") (pintype "passive"))
      (node (ref "U1") (pin "60") (pinfunction "TXVDDVCO18_60") (pintype "passive"))
    )
    (net (code "18") (name "/VSPI18") (class "Default")
      (node (ref "C12") (pin "2") (pinfunction "2_2") (pintype "passive"))
      (node (ref "FB3") (pin "1") (pinfunction "1_1") (pintype "passive"))
      (node (ref "U1") (pin "72") (pinfunction "TRXVDDDSM18_72") (pintype "passive"))
      (node (ref "U1") (pin "73") (pinfunction "VSPI18_73") (pintype "passive"))
    )
    (net (code "19") (name "GND") (class "Default")
      (node (ref "C10") (pin "1") (pinfunction "1_1") (pintype "passive"))
      (node (ref "C11") (pin "1") (pinfunction "1_1") (pintype "passive"))
      (node (ref "C12") (pin "1") (pinfunction "1_1") (pintype "passive"))
      (node (ref "C129") (pin "1") (pinfunction "1_1") (pintype "passive"))
      (node (ref "C13") (pin "2") (pinfunction "2_2") (pintype "passive"))
      (node (ref "C130") (pin "1") (pinfunction "1_1") (pintype "passive"))
      (node (ref "C131") (pin "1") (pinfunction "1_1") (pintype "passive"))
      (node (ref "C132") (pin "1") (pinfunction "1_1") (pintype "passive"))
      (node (ref "C133") (pin "1") (pinfunction "1_1") (pintype "passive"))
      (node (ref "C134") (pin "1") (pinfunction "1_1") (pintype "passive"))
      (node (ref "C135") (pin "1") (pinfunction "1_1") (pintype "passive"))
      (node (ref "C14") (pin "1") (pinfunction "1_1") (pintype "passive"))
      (node (ref "C15") (pin "1") (pinfunction "1_1") (pintype "passive"))
      (node (ref "C16") (pin "2") (pinfunction "2_2") (pintype "passive"))
      (node (ref "C17") (pin "1") (pinfunction "1_1") (pintype "passive"))
      (node (ref "C18") (pin "1") (pinfunction "1_1") (pintype "passive"))
      (node (ref "C19") (pin "2") (pinfunction "2_2") (pintype "passive"))
      (node (ref "C20") (pin "1") (pinfunction "1_1") (pintype "passive"))
      (node (ref "C21") (pin "2") (pinfunction "2_2") (pintype "passive"))
      (node (ref "C22") (pin "1") (pinfunction "1_1") (pintype "passive"))
      (node (ref "C23") (pin "2") (pinfunction "2_2") (pintype "passive"))
      (node (ref "C24") (pin "1") (pinfunction "1_1") (pintype "passive"))
      (node (ref "C25") (pin "1") (pinfunction "1_1") (pintype "passive"))
      (node (ref "C26") (pin "2") (pinfunction "2_2") (pintype "passive"))
      (node (ref "C27") (pin "1") (pinfunction "1_1") (pintype "passive"))
      (node (ref "C28") (pin "2") (pinfunction "2_2") (pintype "passive"))
      (node (ref "C29") (pin "2") (pinfunction "2_2") (pintype "passive"))
      (node (ref "C30") (pin "1") (pinfunction "1_1") (pintype "passive"))
      (node (ref "C31") (pin "2") (pinfunction "2_2") (pintype "passive"))
      (node (ref "C32") (pin "1") (pinfunction "1_1") (pintype "passive"))
      (node (ref "C34") (pin "1") (pinfunction "1_1") (pintype "passive"))
      (node (ref "C35") (pin "2") (pinfunction "2_2") (pintype "passive"))
      (node (ref "C36") (pin "2") (pinfunction "2_2") (pintype "passive"))
      (node (ref "C37") (pin "1") (pinfunction "1_1") (pintype "passive"))
      (node (ref "C38") (pin "2") (pinfunction "2_2") (pintype "passive"))
      (node (ref "C39") (pin "1") (pinfunction "1_1") (pintype "passive"))
      (node (ref "C40") (pin "1") (pinfunction "1_1") (pintype "passive"))
      (node (ref "C41") (pin "1") (pinfunction "1_1") (pintype "passive"))
      (node (ref "C42") (pin "1") (pinfunction "1_1") (pintype "passive"))
      (node (ref "C43") (pin "1") (pinfunction "1_1") (pintype "passive"))
      (node (ref "C44") (pin "2") (pinfunction "2_2") (pintype "passive"))
      (node (ref "C45") (pin "2") (pinfunction "2_2") (pintype "passive"))
      (node (ref "C46") (pin "2") (pinfunction "2_2") (pintype "passive"))
      (node (ref "C47") (pin "1") (pinfunction "1_1") (pintype "passive"))
      (node (ref "C5") (pin "2") (pinfunction "2_2") (pintype "passive"))
      (node (ref "C6") (pin "1") (pinfunction "1_1") (pintype "passive"))
      (node (ref "C79") (pin "1") (pinfunction "1_1") (pintype "passive"))
      (node (ref "C80") (pin "1") (pinfunction "1_1") (pintype "passive"))
      (node (ref "C9") (pin "1") (pinfunction "1_1") (pintype "passive"))
      (node (ref "D1") (pin "-") (pinfunction "Cathode_-") (pintype "power_in"))
      (node (ref "D2") (pin "-") (pinfunction "Cathode_-") (pintype "power_in"))
      (node (ref "D3") (pin "-") (pinfunction "Cathode_-") (pintype "power_in"))
      (node (ref "D4") (pin "-") (pinfunction "Cathode_-") (pintype "power_in"))
      (node (ref "IC4") (pin "2") (pinfunction "GND_2") (pintype "passive"))
      (node (ref "J1") (pin "1") (pinfunction "1_1") (pintype "passive"))
      (node (ref "J2") (pin "1") (pinfunction "1_1") (pintype "passive"))
      (node (ref "U1") (pin "121") (pinfunction "GND_121") (pintype "passive"))
      (node (ref "U2") (pin "2") (pinfunction "GND_2") (pintype "passive"))
      (node (ref "U3") (pin "2") (pinfunction "COMMON_2") (pintype "passive"))
      (node (ref "U4") (pin "2") (pinfunction "COMMON_2") (pintype "passive"))
      (node (ref "U6") (pin "2") (pinfunction "GND_2") (pintype "passive"))
      (node (ref "U8") (pin "2") (pinfunction "GND_2") (pintype "passive"))
    )
    (net (code "20") (name "HSMC_VADJ") (class "Default")
      (node (ref "R102") (pin "2") (pinfunction "2_2") (pintype "passive"))
      (node (ref "R59") (pin "1") (pinfunction "1_1") (pintype "passive"))
    )
    (net (code "21") (name "Net-(D1-Anode)") (class "Default")
      (node (ref "D1") (pin "+") (pinfunction "Anode_+") (pintype "power_in"))
      (node (ref "R42") (pin "1") (pinfunction "1_1") (pintype "passive"))
    )
    (net (code "22") (name "Net-(D2-Anode)") (class "Default")
      (node (ref "D2") (pin "+") (pinfunction "Anode_+") (pintype "power_in"))
      (node (ref "R43") (pin "1") (pinfunction "1_1") (pintype "passive"))
    )
    (net (code "23") (name "Net-(D3-Anode)") (class "Default")
      (node (ref "D3") (pin "+") (pinfunction "Anode_+") (pintype "power_in"))
      (node (ref "R44") (pin "1") (pinfunction "1_1") (pintype "passive"))
    )
    (net (code "24") (name "Net-(D4-Anode)") (class "Default")
      (node (ref "D4") (pin "+") (pinfunction "Anode_+") (pintype "power_in"))
      (node (ref "R45") (pin "1") (pinfunction "1_1") (pintype "passive"))
    )
    (net (code "25") (name "Net-(FB11-Pad2)") (class "Default")
      (node (ref "FB11") (pin "2") (pinfunction "2_2") (pintype "passive"))
      (node (ref "R1") (pin "2") (pinfunction "2_2") (pintype "passive"))
    )
    (net (code "26") (name "Net-(FB13-Pad2)") (class "Default")
      (node (ref "FB13") (pin "2") (pinfunction "2_2") (pintype "passive"))
      (node (ref "R2") (pin "2") (pinfunction "2_2") (pintype "passive"))
    )
    (net (code "27") (name "Net-(FB15-Pad1)") (class "Default")
      (node (ref "FB15") (pin "1") (pinfunction "1_1") (pintype "passive"))
      (node (ref "R58") (pin "2") (pinfunction "2_2") (pintype "passive"))
      (node (ref "R59") (pin "2") (pinfunction "2_2") (pintype "passive"))
    )
    (net (code "28") (name "Net-(IC4-EN)") (class "Default")
      (node (ref "C133") (pin "2") (pinfunction "2_2") (pintype "passive"))
      (node (ref "FB23") (pin "1") (pinfunction "1_1") (pintype "passive"))
      (node (ref "IC4") (pin "1") (pinfunction "IN_1") (pintype "passive"))
      (node (ref "IC4") (pin "3") (pinfunction "EN_3") (pintype "passive"))
    )
    (net (code "29") (name "Net-(IC4-NR{slash}FB)") (class "Default")
      (node (ref "C134") (pin "2") (pinfunction "2_2") (pintype "passive"))
      (node (ref "IC4") (pin "4") (pinfunction "NR/FB_4") (pintype "passive"))
    )
    (net (code "30") (name "Net-(U1A-RXVCCPLL18)") (class "Default")
      (node (ref "C13") (pin "1") (pinfunction "1_1") (pintype "passive"))
      (node (ref "C14") (pin "2") (pinfunction "2_2") (pintype "passive"))
      (node (ref "FB4") (pin "1") (pinfunction "1_1") (pintype "passive"))
      (node (ref "U1") (pin "83") (pinfunction "RXVCCPLL18_83") (pintype "passive"))
    )
    (net (code "31") (name "Net-(U2-BYPASS)") (class "Default")
      (node (ref "C17") (pin "2") (pinfunction "2_2") (pintype "passive"))
      (node (ref "U2") (pin "4") (pinfunction "BYPASS_4") (pintype "passive"))
    )
    (net (code "32") (name "Net-(U2-ON{slash}OFF)") (class "Default")
      (node (ref "C15") (pin "2") (pinfunction "2_2") (pintype "passive"))
      (node (ref "FB7") (pin "1") (pinfunction "1_1") (pintype "passive"))
      (node (ref "U2") (pin "1") (pinfunction "Vin_1") (pintype "passive"))
      (node (ref "U2") (pin "3") (pinfunction "ON/OFF_3") (pintype "passive"))
    )
    (net (code "33") (name "Net-(U3-INPUT)") (class "Default")
      (node (ref "C44") (pin "1") (pinfunction "1_1") (pintype "passive"))
      (node (ref "FB18") (pin "2") (pinfunction "2_2") (pintype "passive"))
      (node (ref "U3") (pin "1") (pinfunction "INPUT_1") (pintype "passive"))
    )
    (net (code "34") (name "Net-(U4-INPUT)") (class "Default")
      (node (ref "C46") (pin "1") (pinfunction "1_1") (pintype "passive"))
      (node (ref "FB19") (pin "2") (pinfunction "2_2") (pintype "passive"))
      (node (ref "U4") (pin "1") (pinfunction "INPUT_1") (pintype "passive"))
    )
    (net (code "35") (name "Net-(U6-BYPASS)") (class "Default")
      (node (ref "C129") (pin "2") (pinfunction "2_2") (pintype "passive"))
      (node (ref "U6") (pin "4") (pinfunction "BYPASS_4") (pintype "passive"))
    )
    (net (code "36") (name "Net-(U6-ON{slash}OFF)") (class "Default")
      (node (ref "C79") (pin "2") (pinfunction "2_2") (pintype "passive"))
      (node (ref "FB24") (pin "1") (pinfunction "1_1") (pintype "passive"))
      (node (ref "U6") (pin "1") (pinfunction "Vin_1") (pintype "passive"))
      (node (ref "U6") (pin "3") (pinfunction "ON/OFF_3") (pintype "passive"))
    )
    (net (code "37") (name "Net-(U8-BYPASS)") (class "Default")
      (node (ref "C132") (pin "2") (pinfunction "2_2") (pintype "passive"))
      (node (ref "U8") (pin "4") (pinfunction "BYPASS_4") (pintype "passive"))
    )
    (net (code "38") (name "Net-(U8-ON{slash}OFF)") (class "Default")
      (node (ref "C130") (pin "2") (pinfunction "2_2") (pintype "passive"))
      (node (ref "FB25") (pin "1") (pinfunction "1_1") (pintype "passive"))
      (node (ref "U8") (pin "1") (pinfunction "Vin_1") (pintype "passive"))
      (node (ref "U8") (pin "3") (pinfunction "ON/OFF_3") (pintype "passive"))
    )
    (net (code "39") (name "VCC_1.8V") (class "Default")
      (node (ref "C18") (pin "2") (pinfunction "2_2") (pintype "passive"))
      (node (ref "FB1") (pin "2") (pinfunction "2_2") (pintype "passive"))
      (node (ref "FB2") (pin "2") (pinfunction "2_2") (pintype "passive"))
      (node (ref "FB3") (pin "2") (pinfunction "2_2") (pintype "passive"))
      (node (ref "FB4") (pin "2") (pinfunction "2_2") (pintype "passive"))
      (node (ref "FB5") (pin "2") (pinfunction "2_2") (pintype "passive"))
      (node (ref "U2") (pin "5") (pinfunction "Vout_5") (pintype "passive"))
    )
    (net (code "40") (name "VCC_1.8V_RXVCO") (class "Default")
      (node (ref "C131") (pin "2") (pinfunction "2_2") (pintype "passive"))
      (node (ref "FB13") (pin "1") (pinfunction "1_1") (pintype "passive"))
      (node (ref "U8") (pin "5") (pinfunction "Vout_5") (pintype "passive"))
    )
    (net (code "41") (name "VCC_1.8V_TXVCO") (class "Default")
      (node (ref "C80") (pin "2") (pinfunction "2_2") (pintype "passive"))
      (node (ref "FB11") (pin "1") (pinfunction "1_1") (pintype "passive"))
      (node (ref "U6") (pin "5") (pinfunction "Vout_5") (pintype "passive"))
    )
    (net (code "42") (name "VCC_3.3V") (class "Default")
      (node (ref "C40") (pin "2") (pinfunction "2_2") (pintype "passive"))
      (node (ref "FB10") (pin "2") (pinfunction "2_2") (pintype "passive"))
      (node (ref "FB12") (pin "2") (pinfunction "2_2") (pintype "passive"))
      (node (ref "FB14") (pin "1") (pinfunction "1_1") (pintype "passive"))
      (node (ref "FB16") (pin "2") (pinfunction "2_2") (pintype "passive"))
      (node (ref "FB17") (pin "1") (pinfunction "1_1") (pintype "passive"))
      (node (ref "FB24") (pin "2") (pinfunction "2_2") (pintype "passive"))
      (node (ref "FB25") (pin "2") (pinfunction "2_2") (pintype "passive"))
      (node (ref "FB6") (pin "2") (pinfunction "2_2") (pintype "passive"))
      (node (ref "FB7") (pin "2") (pinfunction "2_2") (pintype "passive"))
      (node (ref "FB8") (pin "2") (pinfunction "2_2") (pintype "passive"))
      (node (ref "FB9") (pin "2") (pinfunction "2_2") (pintype "passive"))
      (node (ref "J1") (pin "2") (pinfunction "2_2") (pintype "passive"))
      (node (ref "R103") (pin "2") (pinfunction "2_2") (pintype "passive"))
      (node (ref "R39") (pin "1") (pinfunction "1_1") (pintype "passive"))
      (node (ref "R40") (pin "1") (pinfunction "1_1") (pintype "passive"))
      (node (ref "R45") (pin "2") (pinfunction "2_2") (pintype "passive"))
      (node (ref "R58") (pin "1") (pinfunction "1_1") (pintype "passive"))
    )
    (net (code "43") (name "VCC_5V") (class "Default")
      (node (ref "C45") (pin "1") (pinfunction "1_1") (pintype "passive"))
      (node (ref "FB23") (pin "2") (pinfunction "2_2") (pintype "passive"))
      (node (ref "R44") (pin "2") (pinfunction "2_2") (pintype "passive"))
      (node (ref "U3") (pin "3") (pinfunction "OUTPUT_3") (pintype "passive"))
    )
    (net (code "44") (name "VCC_7V") (class "Default")
      (node (ref "C47") (pin "2") (pinfunction "2_2") (pintype "passive"))
      (node (ref "R43") (pin "2") (pinfunction "2_2") (pintype "passive"))
      (node (ref "U4") (pin "3") (pinfunction "OUTPUT_3") (pintype "passive"))
    )
    (net (code "45") (name "VCC_12V") (class "Default")
      (node (ref "FB18") (pin "1") (pinfunction "1_1") (pintype "passive"))
      (node (ref "FB19") (pin "1") (pinfunction "1_1") (pintype "passive"))
      (node (ref "J2") (pin "2") (pinfunction "2_2") (pintype "passive"))
      (node (ref "R42") (pin "2") (pinfunction "2_2") (pintype "passive"))
    )
    (net (code "46") (name "VREG_2.85V") (class "Default")
      (node (ref "C135") (pin "2") (pinfunction "2_2") (pintype "passive"))
      (node (ref "IC4") (pin "5") (pinfunction "OUT_5") (pintype "passive"))
    )
    (net (code "47") (name "unconnected-(C33-Pad1)") (class "Default")
      (node (ref "C33") (pin "1") (pinfunction "1_1") (pintype "passive"))
    )
  )
)
